# Sheet2.net
KiCad netlist of a schematic drawn in Altium Designer
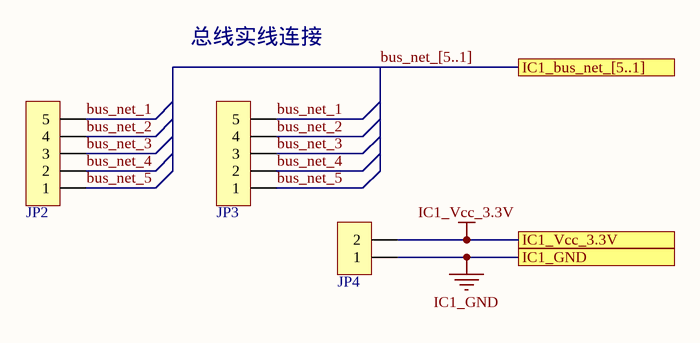
[diagram p0: Sheet2.SchDoc]

(export (version "E")
  (design (tool "Eeschema 10.0.6"))
  (components
    (comp (ref "JP2")
      (value "HDR-1X5")
      (footprint "HDR2.54-LI-5P")
      (description "5P接插件")
      (fields (field (name "版权归属") "源创客"))
      (libsource (lib "4.6   - 接插件-脚距2.54") (part "Header 5"))
    )
    (comp (ref "JP3")
      (value "HDR-1X5")
      (footprint "HDR2.54-LI-5P")
      (description "5P接插件")
      (fields (field (name "版权归属") "源创客"))
      (libsource (lib "4.6   - 接插件-脚距2.54") (part "Header 5"))
    )
    (comp (ref "JP4")
      (value "HDR-1X2")
      (footprint "HDR2.54-LI-2P")
      (description "2P接插件")
      (fields (field (name "版权归属") "源创客"))
      (libsource (lib "4.6   - 接插件-脚距2.54") (part "Header 2"))
    )
  )
  (nets
    (net (code "1") (name "/bus_net_1") (class "Default")
      (node (ref "JP2") (pin "5") (pinfunction "5_5") (pintype "passive"))
      (node (ref "JP3") (pin "5") (pinfunction "5_5") (pintype "passive"))
    )
    (net (code "2") (name "/bus_net_2") (class "Default")
      (node (ref "JP2") (pin "4") (pinfunction "4_4") (pintype "passive"))
      (node (ref "JP3") (pin "4") (pinfunction "4_4") (pintype "passive"))
    )
    (net (code "3") (name "/bus_net_3") (class "Default")
      (node (ref "JP2") (pin "3") (pinfunction "3_3") (pintype "passive"))
      (node (ref "JP3") (pin "3") (pinfunction "3_3") (pintype "passive"))
    )
    (net (code "4") (name "/bus_net_4") (class "Default")
      (node (ref "JP2") (pin "2") (pinfunction "2_2") (pintype "passive"))
      (node (ref "JP3") (pin "2") (pinfunction "2_2") (pintype "passive"))
    )
    (net (code "5") (name "/bus_net_5") (class "Default")
      (node (ref "JP2") (pin "1") (pinfunction "1_1") (pintype "passive"))
      (node (ref "JP3") (pin "1") (pinfunction "1_1") (pintype "passive"))
    )
    (net (code "7") (name "IC1_GND") (class "Default")
      (node (ref "JP4") (pin "1") (pinfunction "1_1") (pintype "passive"))
    )
    (net (code "8") (name "IC1_Vcc_3.3V") (class "Default")
      (node (ref "JP4") (pin "2") (pinfunction "2_2") (pintype "passive"))
    )
  )
)
